# sxem.net
KiCad netlist of a schematic drawn in Altium Designer
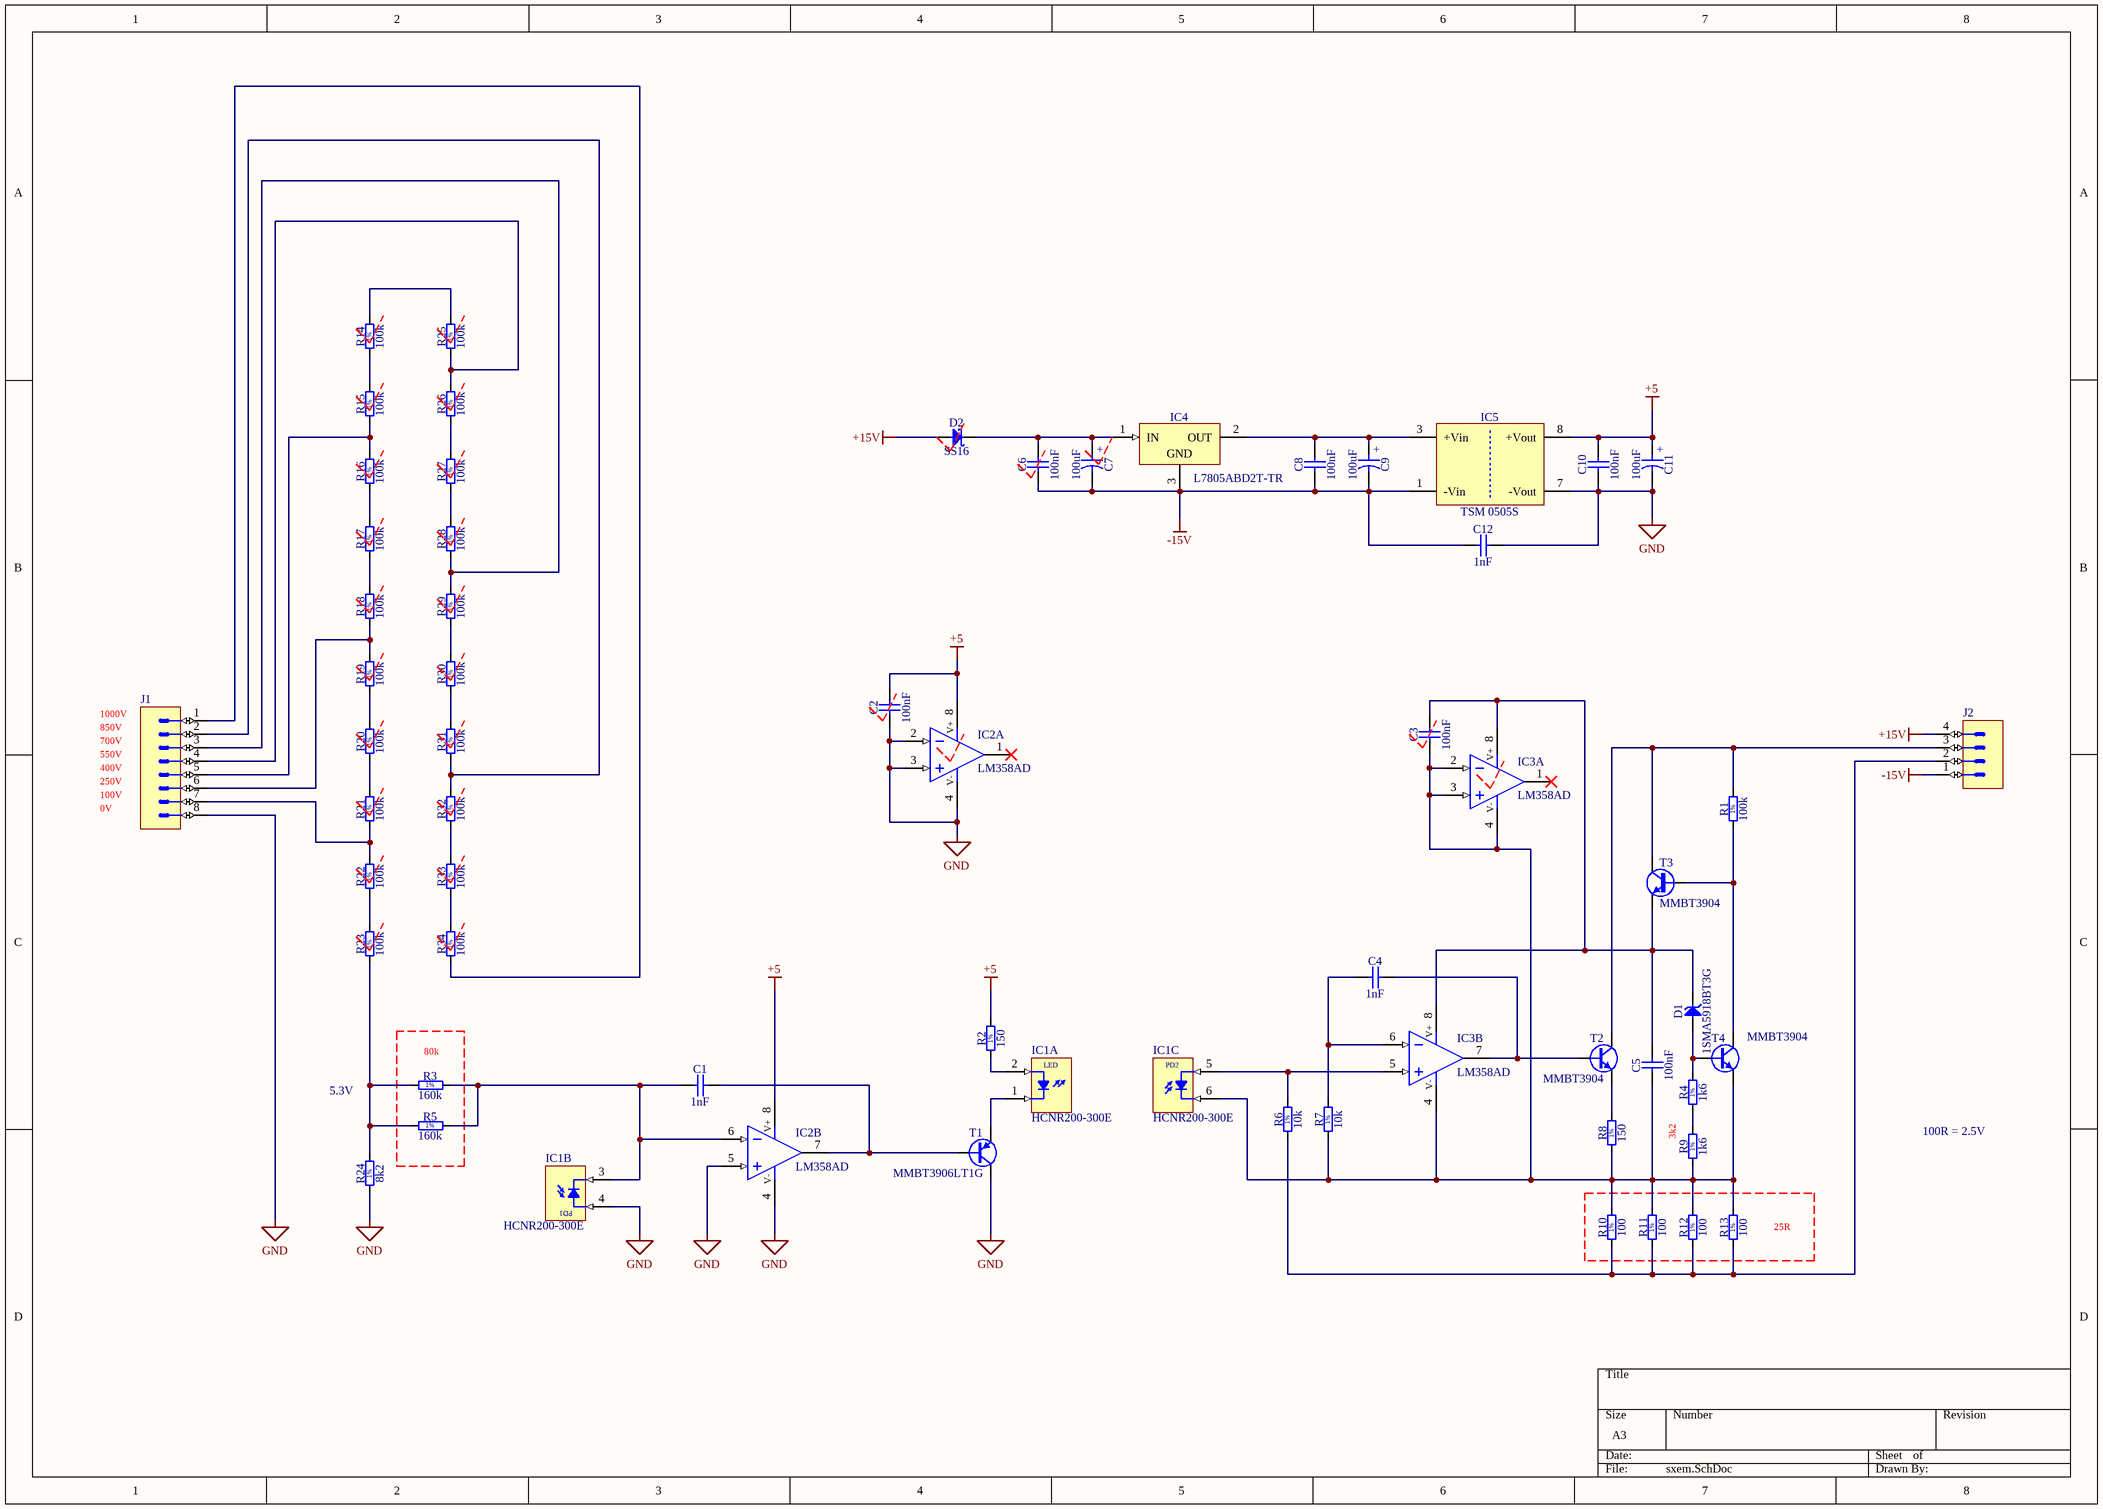
[diagram p0: sxem.SchDoc]

(export (version "E")
  (design (tool "Eeschema 10.0.6"))
  (components
    (comp (ref "C1")
      (value "1nF")
      (footprint "CAPC3216X140N")
      (description "Non-polarised capacitor")
      (fields
        (field (name "PART NUMBER") "CC1206_1NF_100V_5%_NP0")
        (field (name "VOLTAGE") "100V")
        (field (name "AUTHOR") "CERN DEM JLC")
      )
      (libsource (lib "Capacitors") (part "Capacitor - non polarized"))
    )
    (comp (ref "C2")
      (value "100nF")
      (footprint "CAPC3216X140N")
      (description "Non-polarised capacitor")
      (fields
        (field (name "PART NUMBER") "CC1206_100NF_100V_10%_X7R")
        (field (name "VOLTAGE") "100V")
        (field (name "AUTHOR") "CERN DEM JLC")
      )
      (libsource (lib "Capacitors") (part "Capacitor - non polarized"))
    )
    (comp (ref "C3")
      (value "100nF")
      (footprint "CAPC3216X140N")
      (description "Non-polarised capacitor")
      (fields
        (field (name "PART NUMBER") "CC1206_100NF_100V_10%_X7R")
        (field (name "VOLTAGE") "100V")
        (field (name "AUTHOR") "CERN DEM JLC")
      )
      (libsource (lib "Capacitors") (part "Capacitor - non polarized"))
    )
    (comp (ref "C4")
      (value "1nF")
      (footprint "CAPC3216X140N")
      (description "Non-polarised capacitor")
      (fields
        (field (name "PART NUMBER") "CC1206_1NF_100V_5%_NP0")
        (field (name "VOLTAGE") "100V")
        (field (name "AUTHOR") "CERN DEM JLC")
      )
      (libsource (lib "Capacitors") (part "Capacitor - non polarized"))
    )
    (comp (ref "C5")
      (value "100nF")
      (footprint "CAPC3216X140N")
      (description "Non-polarised capacitor")
      (fields
        (field (name "PART NUMBER") "CC1206_100NF_100V_10%_X7R")
        (field (name "VOLTAGE") "100V")
        (field (name "AUTHOR") "CERN DEM JLC")
      )
      (libsource (lib "Capacitors") (part "Capacitor - non polarized"))
    )
    (comp (ref "C6")
      (value "100nF")
      (footprint "CAPC3216X140N")
      (description "Non-polarised capacitor")
      (fields
        (field (name "PART NUMBER") "CC1206_100NF_100V_10%_X7R")
        (field (name "VOLTAGE") "100V")
        (field (name "AUTHOR") "CERN DEM JLC")
      )
      (libsource (lib "Capacitors") (part "Capacitor - non polarized"))
    )
    (comp (ref "C7")
      (value "100uF")
      (footprint "CAPPR250-680X1250")
      (description "Polarised capacitor")
      (fields
        (field (name "PART NUMBER") "CAER_100UF_25V_20%_NICHICON_UPS1E101MED")
        (field (name "VOLTAGE") "25V")
        (field (name "AUTHOR") "CERN DEM MR")
      )
      (libsource (lib "Capacitors") (part "Capacitor - polarized"))
    )
    (comp (ref "C8")
      (value "100nF")
      (footprint "CAPC3216X140N")
      (description "Non-polarised capacitor")
      (fields
        (field (name "PART NUMBER") "CC1206_100NF_100V_10%_X7R")
        (field (name "VOLTAGE") "100V")
        (field (name "AUTHOR") "CERN DEM JLC")
      )
      (libsource (lib "Capacitors") (part "Capacitor - non polarized"))
    )
    (comp (ref "C9")
      (value "100uF")
      (footprint "CAPPR250-680X1080")
      (description "Polarised capacitor")
      (fields
        (field (name "PART NUMBER") "CAER_100UF_16V_20%_CHEMI-CON_APSA160ELL101MFA5G")
        (field (name "VOLTAGE") "16V")
        (field (name "AUTHOR") "CERN DEM JLC")
      )
      (libsource (lib "Capacitors") (part "Capacitor - polarized"))
    )
    (comp (ref "C10")
      (value "100nF")
      (footprint "CAPC3216X140N")
      (description "Non-polarised capacitor")
      (fields
        (field (name "PART NUMBER") "CC1206_100NF_100V_10%_X7R")
        (field (name "VOLTAGE") "100V")
        (field (name "AUTHOR") "CERN DEM JLC")
      )
      (libsource (lib "Capacitors") (part "Capacitor - non polarized"))
    )
    (comp (ref "C11")
      (value "100uF")
      (footprint "CAPPR250-680X1080")
      (description "Polarised capacitor")
      (fields
        (field (name "PART NUMBER") "CAER_100UF_16V_20%_CHEMI-CON_APSA160ELL101MFA5G")
        (field (name "VOLTAGE") "16V")
        (field (name "AUTHOR") "CERN DEM JLC")
      )
      (libsource (lib "Capacitors") (part "Capacitor - polarized"))
    )
    (comp (ref "C12")
      (value "1nF")
      (footprint "CAPRB_MURATA_DHR4E4C102K2FB")
      (description "Non-polarised capacitor")
      (fields
        (field (name "PART NUMBER") "CCR_1NF_15KV_10%_MURATA_DHR4E4C102K2FB")
        (field (name "VOLTAGE") "15kV")
        (field (name "AUTHOR") "CERN DEM JLC")
      )
      (libsource (lib "Capacitors") (part "Capacitor - non polarized"))
    )
    (comp (ref "D1")
      (value "1SMA5918BT3G")
      (footprint "DIOM5226X230N")
      (description "Zener Diode")
      (fields
        (field (name "VOLTAGE") "5.1V")
        (field (name "POWER") "1.5W")
        (field (name "AUTHOR") "CERN DEM JLC")
      )
      (libsource (lib "ICs And Semiconductors") (part "Diode Zener"))
    )
    (comp (ref "D2")
      (value "SS16")
      (footprint "DIOM5127X229N")
      (description "Schottky Diode")
      (fields
        (field (name "VOLTAGE") "60V")
        (field (name "POWER") "1A")
        (field (name "AUTHOR") "CERN DEM JLC")
      )
      (libsource (lib "ICs And Semiconductors") (part "Diode Schottky"))
    )
    (comp (ref "IC1")
      (value "HCNR200-300E")
      (footprint "AVAGO_HCNR200-300E")
      (description "High-Linearity Analog Optocoupler")
      (fields (field (name "MANUFACTURER") "AVAGO TECHNOLOGIES") (field (name "AUTHOR") "CERN DEM JLC"))
      (libsource (lib "") (part "Optocoupler Type12_2"))
    )
    (comp (ref "IC2")
      (value "LM358AD")
      (footprint "SOIC127P600X175-8N")
      (description "Dual Operational Amplifier")
      (fields (field (name "MANUFACTURER") "TEXAS INSTRUMENTS") (field (name "AUTHOR") "CERN DEM JLC"))
      (libsource (lib "ICs And Semiconductors") (part "Operational Amplifier x2 Type1"))
    )
    (comp (ref "IC3")
      (value "LM358AD")
      (footprint "SOIC127P600X175-8N")
      (description "Dual Operational Amplifier")
      (fields (field (name "MANUFACTURER") "TEXAS INSTRUMENTS") (field (name "AUTHOR") "CERN DEM JLC"))
      (libsource (lib "ICs And Semiconductors") (part "Operational Amplifier x2 Type1"))
    )
    (comp (ref "IC4")
      (value "L7805ABD2T-TR")
      (footprint "TO254P1542X460-3N-R790X1040")
      (description "3-Terminal Regulator 1=IN 2=OUT 3=GND")
      (fields (field (name "MANUFACTURER") "ST MICROELECTRONICS") (field (name "AUTHOR") "CERN DEM JLC"))
      (libsource (lib "ICs And Semiconductors") (part "REG3 1IN-2OUT-3GND"))
    )
    (comp (ref "IC5")
      (value "TSM 0505S")
      (footprint "SOIC127P1110X695-8_14N")
      (description "TRACO, TSM Serie, Single Output DCDC Converter")
      (fields (field (name "MANUFACTURER") "TRACO POWER") (field (name "AUTHOR") "CERN DEM JLC"))
      (libsource (lib "ICs And Semiconductors") (part "DCDC_TRACO_TSM_Single Output"))
    )
    (comp (ref "J1")
      (value "~")
      (footprint "PHOENIX_1757307")
      (description "Connector 8 Male")
      (fields
        (field (name "PART NUMBER") "PHOENIX_1757307")
        (field (name "MANUFACTURER") "PHOENIX CONTACT")
        (field (name "AUTHOR") "CERN DEM JLC")
      )
      (libsource (lib "Connectors") (part "Connector 8 Male"))
    )
    (comp (ref "J2")
      (value "~")
      (footprint "PHOENIX_1757268")
      (description "Connector 4 Male")
      (fields
        (field (name "PART NUMBER") "PHOENIX_1757268")
        (field (name "MANUFACTURER") "PHOENIX CONTACT")
        (field (name "AUTHOR") "CERN DEM JLC")
      )
      (libsource (lib "Connectors") (part "Connector 4 Male"))
    )
    (comp (ref "R1")
      (value "100k")
      (footprint "RESC3216X65N")
      (description "Resistor - 1%")
      (fields
        (field (name "PART NUMBER") "R1206_100K_1%_0.25W_100PPM")
        (field (name "POWER") "0.25W")
        (field (name "AUTHOR") "CERN DEM JLC")
      )
      (libsource (lib "Resistors") (part "Resistor - 1%"))
    )
    (comp (ref "R2")
      (value "150")
      (footprint "RESC3216X65N")
      (description "Resistor - 1%")
      (fields
        (field (name "PART NUMBER") "R1206_150R_1%_0.25W_100PPM")
        (field (name "POWER") "0.25W")
        (field (name "AUTHOR") "CERN DEM JLC")
      )
      (libsource (lib "Resistors") (part "Resistor - 1%"))
    )
    (comp (ref "R3")
      (value "160k")
      (footprint "RESC3216X65N")
      (description "Resistor - 1%")
      (fields
        (field (name "PART NUMBER") "R1206_160K_1%_0.25W_100PPM")
        (field (name "POWER") "0.25W")
        (field (name "AUTHOR") "CERN DEM JLC")
      )
      (libsource (lib "Resistors") (part "Resistor - 1%"))
    )
    (comp (ref "R4")
      (value "1k6")
      (footprint "RESC3216X65N")
      (description "Resistor - 1%")
      (fields
        (field (name "PART NUMBER") "R1206_1K6_1%_0.25W_100PPM")
        (field (name "POWER") "0.25W")
        (field (name "AUTHOR") "CERN DEM JLC")
      )
      (libsource (lib "Resistors") (part "Resistor - 1%"))
    )
    (comp (ref "R5")
      (value "160k")
      (footprint "RESC3216X65N")
      (description "Resistor - 1%")
      (fields
        (field (name "PART NUMBER") "R1206_160K_1%_0.25W_100PPM")
        (field (name "POWER") "0.25W")
        (field (name "AUTHOR") "CERN DEM JLC")
      )
      (libsource (lib "Resistors") (part "Resistor - 1%"))
    )
    (comp (ref "R6")
      (value "10k")
      (footprint "RESC3216X65N")
      (description "Resistor - 1%")
      (fields
        (field (name "PART NUMBER") "R1206_10K_1%_0.25W_100PPM")
        (field (name "POWER") "0.25W")
        (field (name "AUTHOR") "CERN DEM JLC")
      )
      (libsource (lib "Resistors") (part "Resistor - 1%"))
    )
    (comp (ref "R7")
      (value "10k")
      (footprint "RESC3216X65N")
      (description "Resistor - 1%")
      (fields
        (field (name "PART NUMBER") "R1206_10K_1%_0.25W_100PPM")
        (field (name "POWER") "0.25W")
        (field (name "AUTHOR") "CERN DEM JLC")
      )
      (libsource (lib "Resistors") (part "Resistor - 1%"))
    )
    (comp (ref "R8")
      (value "150")
      (footprint "RESC3216X65N")
      (description "Resistor - 1%")
      (fields
        (field (name "PART NUMBER") "R1206_150R_1%_0.25W_100PPM")
        (field (name "POWER") "0.25W")
        (field (name "AUTHOR") "CERN DEM JLC")
      )
      (libsource (lib "Resistors") (part "Resistor - 1%"))
    )
    (comp (ref "R9")
      (value "1k6")
      (footprint "RESC3216X65N")
      (description "Resistor - 1%")
      (fields
        (field (name "PART NUMBER") "R1206_1K6_1%_0.25W_100PPM")
        (field (name "POWER") "0.25W")
        (field (name "AUTHOR") "CERN DEM JLC")
      )
      (libsource (lib "Resistors") (part "Resistor - 1%"))
    )
    (comp (ref "R10")
      (value "100")
      (footprint "RESC3216X65N")
      (description "Resistor - 1%")
      (fields
        (field (name "PART NUMBER") "R1206_100R_1%_0.25W_100PPM")
        (field (name "POWER") "0.25W")
        (field (name "AUTHOR") "CERN DEM JLC")
      )
      (libsource (lib "Resistors") (part "Resistor - 1%"))
    )
    (comp (ref "R11")
      (value "100")
      (footprint "RESC3216X65N")
      (description "Resistor - 1%")
      (fields
        (field (name "PART NUMBER") "R1206_100R_1%_0.25W_100PPM")
        (field (name "POWER") "0.25W")
        (field (name "AUTHOR") "CERN DEM JLC")
      )
      (libsource (lib "Resistors") (part "Resistor - 1%"))
    )
    (comp (ref "R12")
      (value "100")
      (footprint "RESC3216X65N")
      (description "Resistor - 1%")
      (fields
        (field (name "PART NUMBER") "R1206_100R_1%_0.25W_100PPM")
        (field (name "POWER") "0.25W")
        (field (name "AUTHOR") "CERN DEM JLC")
      )
      (libsource (lib "Resistors") (part "Resistor - 1%"))
    )
    (comp (ref "R13")
      (value "100")
      (footprint "RESC3216X65N")
      (description "Resistor - 1%")
      (fields
        (field (name "PART NUMBER") "R1206_100R_1%_0.25W_100PPM")
        (field (name "POWER") "0.25W")
        (field (name "AUTHOR") "CERN DEM JLC")
      )
      (libsource (lib "Resistors") (part "Resistor - 1%"))
    )
    (comp (ref "R14")
      (value "100k")
      (footprint "RESC3216X65N")
      (description "Resistor - 1%")
      (fields
        (field (name "PART NUMBER") "R1206_100K_1%_0.25W_100PPM")
        (field (name "POWER") "0.25W")
        (field (name "AUTHOR") "CERN DEM JLC")
      )
      (libsource (lib "Resistors") (part "Resistor - 1%"))
    )
    (comp (ref "R15")
      (value "100k")
      (footprint "RESC3216X65N")
      (description "Resistor - 1%")
      (fields
        (field (name "PART NUMBER") "R1206_100K_1%_0.25W_100PPM")
        (field (name "POWER") "0.25W")
        (field (name "AUTHOR") "CERN DEM JLC")
      )
      (libsource (lib "Resistors") (part "Resistor - 1%"))
    )
    (comp (ref "R16")
      (value "100k")
      (footprint "RESC3216X65N")
      (description "Resistor - 1%")
      (fields
        (field (name "PART NUMBER") "R1206_100K_1%_0.25W_100PPM")
        (field (name "POWER") "0.25W")
        (field (name "AUTHOR") "CERN DEM JLC")
      )
      (libsource (lib "Resistors") (part "Resistor - 1%"))
    )
    (comp (ref "R17")
      (value "100k")
      (footprint "RESC3216X65N")
      (description "Resistor - 1%")
      (fields
        (field (name "PART NUMBER") "R1206_100K_1%_0.25W_100PPM")
        (field (name "POWER") "0.25W")
        (field (name "AUTHOR") "CERN DEM JLC")
      )
      (libsource (lib "Resistors") (part "Resistor - 1%"))
    )
    (comp (ref "R18")
      (value "100k")
      (footprint "RESC3216X65N")
      (description "Resistor - 1%")
      (fields
        (field (name "PART NUMBER") "R1206_100K_1%_0.25W_100PPM")
        (field (name "POWER") "0.25W")
        (field (name "AUTHOR") "CERN DEM JLC")
      )
      (libsource (lib "Resistors") (part "Resistor - 1%"))
    )
    (comp (ref "R19")
      (value "100k")
      (footprint "RESC3216X65N")
      (description "Resistor - 1%")
      (fields
        (field (name "PART NUMBER") "R1206_100K_1%_0.25W_100PPM")
        (field (name "POWER") "0.25W")
        (field (name "AUTHOR") "CERN DEM JLC")
      )
      (libsource (lib "Resistors") (part "Resistor - 1%"))
    )
    (comp (ref "R20")
      (value "100k")
      (footprint "RESC3216X65N")
      (description "Resistor - 1%")
      (fields
        (field (name "PART NUMBER") "R1206_100K_1%_0.25W_100PPM")
        (field (name "POWER") "0.25W")
        (field (name "AUTHOR") "CERN DEM JLC")
      )
      (libsource (lib "Resistors") (part "Resistor - 1%"))
    )
    (comp (ref "R21")
      (value "100k")
      (footprint "RESC3216X65N")
      (description "Resistor - 1%")
      (fields
        (field (name "PART NUMBER") "R1206_100K_1%_0.25W_100PPM")
        (field (name "POWER") "0.25W")
        (field (name "AUTHOR") "CERN DEM JLC")
      )
      (libsource (lib "Resistors") (part "Resistor - 1%"))
    )
    (comp (ref "R22")
      (value "100k")
      (footprint "RESC3216X65N")
      (description "Resistor - 1%")
      (fields
        (field (name "PART NUMBER") "R1206_100K_1%_0.25W_100PPM")
        (field (name "POWER") "0.25W")
        (field (name "AUTHOR") "CERN DEM JLC")
      )
      (libsource (lib "Resistors") (part "Resistor - 1%"))
    )
    (comp (ref "R23")
      (value "100k")
      (footprint "RESC3216X65N")
      (description "Resistor - 1%")
      (fields
        (field (name "PART NUMBER") "R1206_100K_1%_0.25W_100PPM")
        (field (name "POWER") "0.25W")
        (field (name "AUTHOR") "CERN DEM JLC")
      )
      (libsource (lib "Resistors") (part "Resistor - 1%"))
    )
    (comp (ref "R24")
      (value "8k2")
      (footprint "RESC3216X65N")
      (description "Resistor - 1%")
      (fields
        (field (name "PART NUMBER") "R1206_8K2_1%_0.25W_100PPM")
        (field (name "POWER") "0.25W")
        (field (name "AUTHOR") "CERN DEM JLC")
      )
      (libsource (lib "Resistors") (part "Resistor - 1%"))
    )
    (comp (ref "R25")
      (value "100k")
      (footprint "RESC3216X65N")
      (description "Resistor - 1%")
      (fields
        (field (name "PART NUMBER") "R1206_100K_1%_0.25W_100PPM")
        (field (name "POWER") "0.25W")
        (field (name "AUTHOR") "CERN DEM JLC")
      )
      (libsource (lib "Resistors") (part "Resistor - 1%"))
    )
    (comp (ref "R26")
      (value "100k")
      (footprint "RESC3216X65N")
      (description "Resistor - 1%")
      (fields
        (field (name "PART NUMBER") "R1206_100K_1%_0.25W_100PPM")
        (field (name "POWER") "0.25W")
        (field (name "AUTHOR") "CERN DEM JLC")
      )
      (libsource (lib "Resistors") (part "Resistor - 1%"))
    )
    (comp (ref "R27")
      (value "100k")
      (footprint "RESC3216X65N")
      (description "Resistor - 1%")
      (fields
        (field (name "PART NUMBER") "R1206_100K_1%_0.25W_100PPM")
        (field (name "POWER") "0.25W")
        (field (name "AUTHOR") "CERN DEM JLC")
      )
      (libsource (lib "Resistors") (part "Resistor - 1%"))
    )
    (comp (ref "R28")
      (value "100k")
      (footprint "RESC3216X65N")
      (description "Resistor - 1%")
      (fields
        (field (name "PART NUMBER") "R1206_100K_1%_0.25W_100PPM")
        (field (name "POWER") "0.25W")
        (field (name "AUTHOR") "CERN DEM JLC")
      )
      (libsource (lib "Resistors") (part "Resistor - 1%"))
    )
    (comp (ref "R29")
      (value "100k")
      (footprint "RESC3216X65N")
      (description "Resistor - 1%")
      (fields
        (field (name "PART NUMBER") "R1206_100K_1%_0.25W_100PPM")
        (field (name "POWER") "0.25W")
        (field (name "AUTHOR") "CERN DEM JLC")
      )
      (libsource (lib "Resistors") (part "Resistor - 1%"))
    )
    (comp (ref "R30")
      (value "100k")
      (footprint "RESC3216X65N")
      (description "Resistor - 1%")
      (fields
        (field (name "PART NUMBER") "R1206_100K_1%_0.25W_100PPM")
        (field (name "POWER") "0.25W")
        (field (name "AUTHOR") "CERN DEM JLC")
      )
      (libsource (lib "Resistors") (part "Resistor - 1%"))
    )
    (comp (ref "R31")
      (value "100k")
      (footprint "RESC3216X65N")
      (description "Resistor - 1%")
      (fields
        (field (name "PART NUMBER") "R1206_100K_1%_0.25W_100PPM")
        (field (name "POWER") "0.25W")
        (field (name "AUTHOR") "CERN DEM JLC")
      )
      (libsource (lib "Resistors") (part "Resistor - 1%"))
    )
    (comp (ref "R32")
      (value "100k")
      (footprint "RESC3216X65N")
      (description "Resistor - 1%")
      (fields
        (field (name "PART NUMBER") "R1206_100K_1%_0.25W_100PPM")
        (field (name "POWER") "0.25W")
        (field (name "AUTHOR") "CERN DEM JLC")
      )
      (libsource (lib "Resistors") (part "Resistor - 1%"))
    )
    (comp (ref "R33")
      (value "100k")
      (footprint "RESC3216X65N")
      (description "Resistor - 1%")
      (fields
        (field (name "PART NUMBER") "R1206_100K_1%_0.25W_100PPM")
        (field (name "POWER") "0.25W")
        (field (name "AUTHOR") "CERN DEM JLC")
      )
      (libsource (lib "Resistors") (part "Resistor - 1%"))
    )
    (comp (ref "R34")
      (value "100k")
      (footprint "RESC3216X65N")
      (description "Resistor - 1%")
      (fields
        (field (name "PART NUMBER") "R1206_100K_1%_0.25W_100PPM")
        (field (name "POWER") "0.25W")
        (field (name "AUTHOR") "CERN DEM JLC")
      )
      (libsource (lib "Resistors") (part "Resistor - 1%"))
    )
    (comp (ref "T1")
      (value "MMBT3906LT1G")
      (footprint "SOT95P240X110-3N")
      (description "PNP Transistor")
      (fields (field (name "MANUFACTURER") "ON SEMICONDUCTOR") (field (name "AUTHOR") "CERN DEM JLC"))
      (libsource (lib "ICs And Semiconductors") (part "PNP B1 E2 C3"))
    )
    (comp (ref "T2")
      (value "MMBT3904")
      (footprint "SOT95P230X110-3N")
      (description "NPN Transistor")
      (fields (field (name "MANUFACTURER") "NXP SEMICONDUCTORS") (field (name "AUTHOR") "CERN DEM JLC"))
      (libsource (lib "ICs And Semiconductors") (part "NPN B1 E2 C3"))
    )
    (comp (ref "T3")
      (value "MMBT3904")
      (footprint "SOT95P230X110-3N")
      (description "NPN Transistor")
      (fields (field (name "MANUFACTURER") "NXP SEMICONDUCTORS") (field (name "AUTHOR") "CERN DEM JLC"))
      (libsource (lib "ICs And Semiconductors") (part "NPN B1 E2 C3"))
    )
    (comp (ref "T4")
      (value "MMBT3904")
      (footprint "SOT95P230X110-3N")
      (description "NPN Transistor")
      (fields (field (name "MANUFACTURER") "NXP SEMICONDUCTORS") (field (name "AUTHOR") "CERN DEM JLC"))
      (libsource (lib "ICs And Semiconductors") (part "NPN B1 E2 C3"))
    )
  )
  (nets
    (net (code "1") (name "+5") (class "Default")
      (node (ref "C10") (pin "2") (pinfunction "2_2") (pintype "passive"))
      (node (ref "C11") (pin "1") (pinfunction "1_1") (pintype "passive"))
      (node (ref "C2") (pin "2") (pinfunction "2_2") (pintype "passive"))
      (node (ref "IC2") (pin "8") (pinfunction "V+_8") (pintype "power_in"))
      (node (ref "IC5") (pin "8") (pinfunction "+Vout_8") (pintype "power_in"))
      (node (ref "R2") (pin "2") (pinfunction "2_2") (pintype "passive"))
    )
    (net (code "2") (name "+15V") (class "Default")
      (node (ref "D2") (pin "2") (pinfunction "A_2") (pintype "passive"))
      (node (ref "J2") (pin "4") (pinfunction "4_4") (pintype "bidirectional"))
    )
    (net (code "3") (name "-15V") (class "Default")
      (node (ref "C12") (pin "1") (pinfunction "1_1") (pintype "passive"))
      (node (ref "C6") (pin "1") (pinfunction "1_1") (pintype "passive"))
      (node (ref "C7") (pin "2") (pinfunction "2_2") (pintype "passive"))
      (node (ref "C8") (pin "1") (pinfunction "1_1") (pintype "passive"))
      (node (ref "C9") (pin "2") (pinfunction "2_2") (pintype "passive"))
      (node (ref "IC4") (pin "3") (pinfunction "GND_3") (pintype "power_in"))
      (node (ref "IC5") (pin "1") (pinfunction "-Vin_1") (pintype "power_in"))
      (node (ref "J2") (pin "1") (pinfunction "1_1") (pintype "bidirectional"))
    )
    (net (code "4") (name "GND") (class "Default")
      (node (ref "C10") (pin "1") (pinfunction "1_1") (pintype "passive"))
      (node (ref "C11") (pin "2") (pinfunction "2_2") (pintype "passive"))
      (node (ref "C12") (pin "2") (pinfunction "2_2") (pintype "passive"))
      (node (ref "C2") (pin "1") (pinfunction "1_1") (pintype "passive"))
      (node (ref "IC1") (pin "4") (pinfunction "A_4") (pintype "input"))
      (node (ref "IC2") (pin "2") (pinfunction "IN-_2") (pintype "input"))
      (node (ref "IC2") (pin "3") (pinfunction "IN+_3") (pintype "input"))
      (node (ref "IC2") (pin "4") (pinfunction "V-_4") (pintype "power_in"))
      (node (ref "IC2") (pin "5") (pinfunction "IN+_5") (pintype "input"))
      (node (ref "IC5") (pin "7") (pinfunction "-Vout_7") (pintype "power_in"))
      (node (ref "J1") (pin "8") (pinfunction "8_8") (pintype "bidirectional"))
      (node (ref "R24") (pin "1") (pinfunction "1_1") (pintype "passive"))
      (node (ref "T1") (pin "3") (pinfunction "C_3") (pintype "passive"))
    )
    (net (code "5") (name "Net-(D1-A)") (class "Default")
      (node (ref "D1") (pin "2") (pinfunction "A_2") (pintype "passive"))
      (node (ref "R4") (pin "2") (pinfunction "2_2") (pintype "passive"))
      (node (ref "T4") (pin "1") (pinfunction "B_1") (pintype "passive"))
    )
    (net (code "6") (name "Net-(D1-C)") (class "Default")
      (node (ref "C3") (pin "2") (pinfunction "2_2") (pintype "passive"))
      (node (ref "C5") (pin "2") (pinfunction "2_2") (pintype "passive"))
      (node (ref "D1") (pin "1") (pinfunction "C_1") (pintype "passive"))
      (node (ref "IC3") (pin "8") (pinfunction "V+_8") (pintype "power_in"))
      (node (ref "T3") (pin "2") (pinfunction "E_2") (pintype "passive"))
    )
    (net (code "7") (name "Net-(D2-C)") (class "Default")
      (node (ref "C6") (pin "2") (pinfunction "2_2") (pintype "passive"))
      (node (ref "C7") (pin "1") (pinfunction "1_1") (pintype "passive"))
      (node (ref "D2") (pin "1") (pinfunction "C_1") (pintype "passive"))
      (node (ref "IC4") (pin "1") (pinfunction "IN_1") (pintype "input"))
    )
    (net (code "8") (name "Net-(IC1A-A)") (class "Default")
      (node (ref "IC1") (pin "2") (pinfunction "A_2") (pintype "input"))
      (node (ref "R2") (pin "1") (pinfunction "1_1") (pintype "passive"))
    )
    (net (code "9") (name "Net-(IC1A-C)") (class "Default")
      (node (ref "IC1") (pin "1") (pinfunction "C_1") (pintype "input"))
      (node (ref "T1") (pin "2") (pinfunction "E_2") (pintype "passive"))
    )
    (net (code "10") (name "Net-(IC1B-C)") (class "Default")
      (node (ref "C1") (pin "1") (pinfunction "1_1") (pintype "passive"))
      (node (ref "IC1") (pin "3") (pinfunction "C_3") (pintype "input"))
      (node (ref "IC2") (pin "6") (pinfunction "IN-_6") (pintype "input"))
      (node (ref "R3") (pin "2") (pinfunction "2_2") (pintype "passive"))
      (node (ref "R5") (pin "2") (pinfunction "2_2") (pintype "passive"))
    )
    (net (code "11") (name "Net-(IC1C-A)") (class "Default")
      (node (ref "IC1") (pin "5") (pinfunction "A_5") (pintype "input"))
      (node (ref "IC3") (pin "5") (pinfunction "IN+_5") (pintype "input"))
      (node (ref "R6") (pin "2") (pinfunction "2_2") (pintype "passive"))
    )
    (net (code "12") (name "Net-(IC1C-C)") (class "Default")
      (node (ref "C3") (pin "1") (pinfunction "1_1") (pintype "passive"))
      (node (ref "C5") (pin "1") (pinfunction "1_1") (pintype "passive"))
      (node (ref "IC1") (pin "6") (pinfunction "C_6") (pintype "input"))
      (node (ref "IC3") (pin "2") (pinfunction "IN-_2") (pintype "input"))
      (node (ref "IC3") (pin "3") (pinfunction "IN+_3") (pintype "input"))
      (node (ref "IC3") (pin "4") (pinfunction "V-_4") (pintype "power_in"))
      (node (ref "R10") (pin "2") (pinfunction "2_2") (pintype "passive"))
      (node (ref "R11") (pin "2") (pinfunction "2_2") (pintype "passive"))
      (node (ref "R12") (pin "2") (pinfunction "2_2") (pintype "passive"))
      (node (ref "R13") (pin "2") (pinfunction "2_2") (pintype "passive"))
      (node (ref "R7") (pin "1") (pinfunction "1_1") (pintype "passive"))
      (node (ref "R8") (pin "1") (pinfunction "1_1") (pintype "passive"))
      (node (ref "R9") (pin "1") (pinfunction "1_1") (pintype "passive"))
      (node (ref "T4") (pin "2") (pinfunction "E_2") (pintype "passive"))
    )
    (net (code "13") (name "Net-(IC2B-OUT)") (class "Default")
      (node (ref "C1") (pin "2") (pinfunction "2_2") (pintype "passive"))
      (node (ref "IC2") (pin "7") (pinfunction "OUT_7") (pintype "open_collector"))
      (node (ref "T1") (pin "1") (pinfunction "B_1") (pintype "passive"))
    )
    (net (code "14") (name "Net-(IC3B-IN-)") (class "Default")
      (node (ref "C4") (pin "1") (pinfunction "1_1") (pintype "passive"))
      (node (ref "IC3") (pin "6") (pinfunction "IN-_6") (pintype "input"))
      (node (ref "R7") (pin "2") (pinfunction "2_2") (pintype "passive"))
    )
    (net (code "15") (name "Net-(IC3B-OUT)") (class "Default")
      (node (ref "C4") (pin "2") (pinfunction "2_2") (pintype "passive"))
      (node (ref "IC3") (pin "7") (pinfunction "OUT_7") (pintype "open_collector"))
      (node (ref "T2") (pin "1") (pinfunction "B_1") (pintype "passive"))
    )
    (net (code "16") (name "Net-(IC4-OUT)") (class "Default")
      (node (ref "C8") (pin "2") (pinfunction "2_2") (pintype "passive"))
      (node (ref "C9") (pin "1") (pinfunction "1_1") (pintype "passive"))
      (node (ref "IC4") (pin "2") (pinfunction "OUT_2") (pintype "power_in"))
      (node (ref "IC5") (pin "3") (pinfunction "+Vin_3") (pintype "power_in"))
    )
    (net (code "17") (name "Net-(J1-Pad1)") (class "Default")
      (node (ref "J1") (pin "1") (pinfunction "1_1") (pintype "bidirectional"))
      (node (ref "R34") (pin "1") (pinfunction "1_1") (pintype "passive"))
    )
    (net (code "18") (name "Net-(J1-Pad2)") (class "Default")
      (node (ref "J1") (pin "2") (pinfunction "2_2") (pintype "bidirectional"))
      (node (ref "R31") (pin "1") (pinfunction "1_1") (pintype "passive"))
      (node (ref "R32") (pin "2") (pinfunction "2_2") (pintype "passive"))
    )
    (net (code "19") (name "Net-(J1-Pad3)") (class "Default")
      (node (ref "J1") (pin "3") (pinfunction "3_3") (pintype "bidirectional"))
      (node (ref "R28") (pin "1") (pinfunction "1_1") (pintype "passive"))
      (node (ref "R29") (pin "2") (pinfunction "2_2") (pintype "passive"))
    )
    (net (code "20") (name "Net-(J1-Pad4)") (class "Default")
      (node (ref "J1") (pin "4") (pinfunction "4_4") (pintype "bidirectional"))
      (node (ref "R25") (pin "1") (pinfunction "1_1") (pintype "passive"))
      (node (ref "R26") (pin "2") (pinfunction "2_2") (pintype "passive"))
    )
    (net (code "21") (name "Net-(J1-Pad5)") (class "Default")
      (node (ref "J1") (pin "5") (pinfunction "5_5") (pintype "bidirectional"))
      (node (ref "R15") (pin "1") (pinfunction "1_1") (pintype "passive"))
      (node (ref "R16") (pin "2") (pinfunction "2_2") (pintype "passive"))
    )
    (net (code "22") (name "Net-(J1-Pad6)") (class "Default")
      (node (ref "J1") (pin "6") (pinfunction "6_6") (pintype "bidirectional"))
      (node (ref "R18") (pin "1") (pinfunction "1_1") (pintype "passive"))
      (node (ref "R19") (pin "2") (pinfunction "2_2") (pintype "passive"))
    )
    (net (code "23") (name "Net-(J1-Pad7)") (class "Default")
      (node (ref "J1") (pin "7") (pinfunction "7_7") (pintype "bidirectional"))
      (node (ref "R21") (pin "1") (pinfunction "1_1") (pintype "passive"))
      (node (ref "R22") (pin "2") (pinfunction "2_2") (pintype "passive"))
    )
    (net (code "24") (name "Net-(J2-Pad2)") (class "Default")
      (node (ref "J2") (pin "2") (pinfunction "2_2") (pintype "bidirectional"))
      (node (ref "R10") (pin "1") (pinfunction "1_1") (pintype "passive"))
      (node (ref "R11") (pin "1") (pinfunction "1_1") (pintype "passive"))
      (node (ref "R12") (pin "1") (pinfunction "1_1") (pintype "passive"))
      (node (ref "R13") (pin "1") (pinfunction "1_1") (pintype "passive"))
      (node (ref "R6") (pin "1") (pinfunction "1_1") (pintype "passive"))
    )
    (net (code "25") (name "Net-(R4-Pad1)") (class "Default")
      (node (ref "R4") (pin "1") (pinfunction "1_1") (pintype "passive"))
      (node (ref "R9") (pin "2") (pinfunction "2_2") (pintype "passive"))
    )
    (net (code "26") (name "Net-(R14-Pad1)") (class "Default")
      (node (ref "R14") (pin "1") (pinfunction "1_1") (pintype "passive"))
      (node (ref "R15") (pin "2") (pinfunction "2_2") (pintype "passive"))
    )
    (net (code "27") (name "Net-(R14-Pad2)") (class "Default")
      (node (ref "R14") (pin "2") (pinfunction "2_2") (pintype "passive"))
      (node (ref "R25") (pin "2") (pinfunction "2_2") (pintype "passive"))
    )
    (net (code "28") (name "Net-(R16-Pad1)") (class "Default")
      (node (ref "R16") (pin "1") (pinfunction "1_1") (pintype "passive"))
      (node (ref "R17") (pin "2") (pinfunction "2_2") (pintype "passive"))
    )
    (net (code "29") (name "Net-(R17-Pad1)") (class "Default")
      (node (ref "R17") (pin "1") (pinfunction "1_1") (pintype "passive"))
      (node (ref "R18") (pin "2") (pinfunction "2_2") (pintype "passive"))
    )
    (net (code "30") (name "Net-(R19-Pad1)") (class "Default")
      (node (ref "R19") (pin "1") (pinfunction "1_1") (pintype "passive"))
      (node (ref "R20") (pin "2") (pinfunction "2_2") (pintype "passive"))
    )
    (net (code "31") (name "Net-(R20-Pad1)") (class "Default")
      (node (ref "R20") (pin "1") (pinfunction "1_1") (pintype "passive"))
      (node (ref "R21") (pin "2") (pinfunction "2_2") (pintype "passive"))
    )
    (net (code "32") (name "Net-(R22-Pad1)") (class "Default")
      (node (ref "R22") (pin "1") (pinfunction "1_1") (pintype "passive"))
      (node (ref "R23") (pin "2") (pinfunction "2_2") (pintype "passive"))
    )
    (net (code "33") (name "Net-(R23-Pad1)") (class "Default")
      (node (ref "R23") (pin "1") (pinfunction "1_1") (pintype "passive"))
      (node (ref "R24") (pin "2") (pinfunction "2_2") (pintype "passive"))
      (node (ref "R3") (pin "1") (pinfunction "1_1") (pintype "passive"))
      (node (ref "R5") (pin "1") (pinfunction "1_1") (pintype "passive"))
    )
    (net (code "34") (name "Net-(R26-Pad1)") (class "Default")
      (node (ref "R26") (pin "1") (pinfunction "1_1") (pintype "passive"))
      (node (ref "R27") (pin "2") (pinfunction "2_2") (pintype "passive"))
    )
    (net (code "35") (name "Net-(R27-Pad1)") (class "Default")
      (node (ref "R27") (pin "1") (pinfunction "1_1") (pintype "passive"))
      (node (ref "R28") (pin "2") (pinfunction "2_2") (pintype "passive"))
    )
    (net (code "36") (name "Net-(R29-Pad1)") (class "Default")
      (node (ref "R29") (pin "1") (pinfunction "1_1") (pintype "passive"))
      (node (ref "R30") (pin "2") (pinfunction "2_2") (pintype "passive"))
    )
    (net (code "37") (name "Net-(R30-Pad1)") (class "Default")
      (node (ref "R30") (pin "1") (pinfunction "1_1") (pintype "passive"))
      (node (ref "R31") (pin "2") (pinfunction "2_2") (pintype "passive"))
    )
    (net (code "38") (name "Net-(R32-Pad1)") (class "Default")
      (node (ref "R32") (pin "1") (pinfunction "1_1") (pintype "passive"))
      (node (ref "R33") (pin "2") (pinfunction "2_2") (pintype "passive"))
    )
    (net (code "39") (name "Net-(R33-Pad1)") (class "Default")
      (node (ref "R33") (pin "1") (pinfunction "1_1") (pintype "passive"))
      (node (ref "R34") (pin "2") (pinfunction "2_2") (pintype "passive"))
    )
    (net (code "40") (name "Net-(T2-C)") (class "Default")
      (node (ref "J2") (pin "3") (pinfunction "3_3") (pintype "bidirectional"))
      (node (ref "R1") (pin "2") (pinfunction "2_2") (pintype "passive"))
      (node (ref "T2") (pin "3") (pinfunction "C_3") (pintype "passive"))
      (node (ref "T3") (pin "3") (pinfunction "C_3") (pintype "passive"))
    )
    (net (code "41") (name "Net-(T2-E)") (class "Default")
      (node (ref "R8") (pin "2") (pinfunction "2_2") (pintype "passive"))
      (node (ref "T2") (pin "2") (pinfunction "E_2") (pintype "passive"))
    )
    (net (code "42") (name "Net-(T3-B)") (class "Default")
      (node (ref "R1") (pin "1") (pinfunction "1_1") (pintype "passive"))
      (node (ref "T3") (pin "1") (pinfunction "B_1") (pintype "passive"))
      (node (ref "T4") (pin "3") (pinfunction "C_3") (pintype "passive"))
    )
    (net (code "43") (name "unconnected-(IC2A-OUT-Pad1)") (class "Default")
      (node (ref "IC2") (pin "1") (pinfunction "OUT_1") (pintype "open_collector+no_connect"))
    )
    (net (code "44") (name "unconnected-(IC3A-OUT-Pad1)") (class "Default")
      (node (ref "IC3") (pin "1") (pinfunction "OUT_1") (pintype "open_collector+no_connect"))
    )
  )
)
